# OSSISolarZ.net
KiCad netlist of a schematic drawn in EAGLE
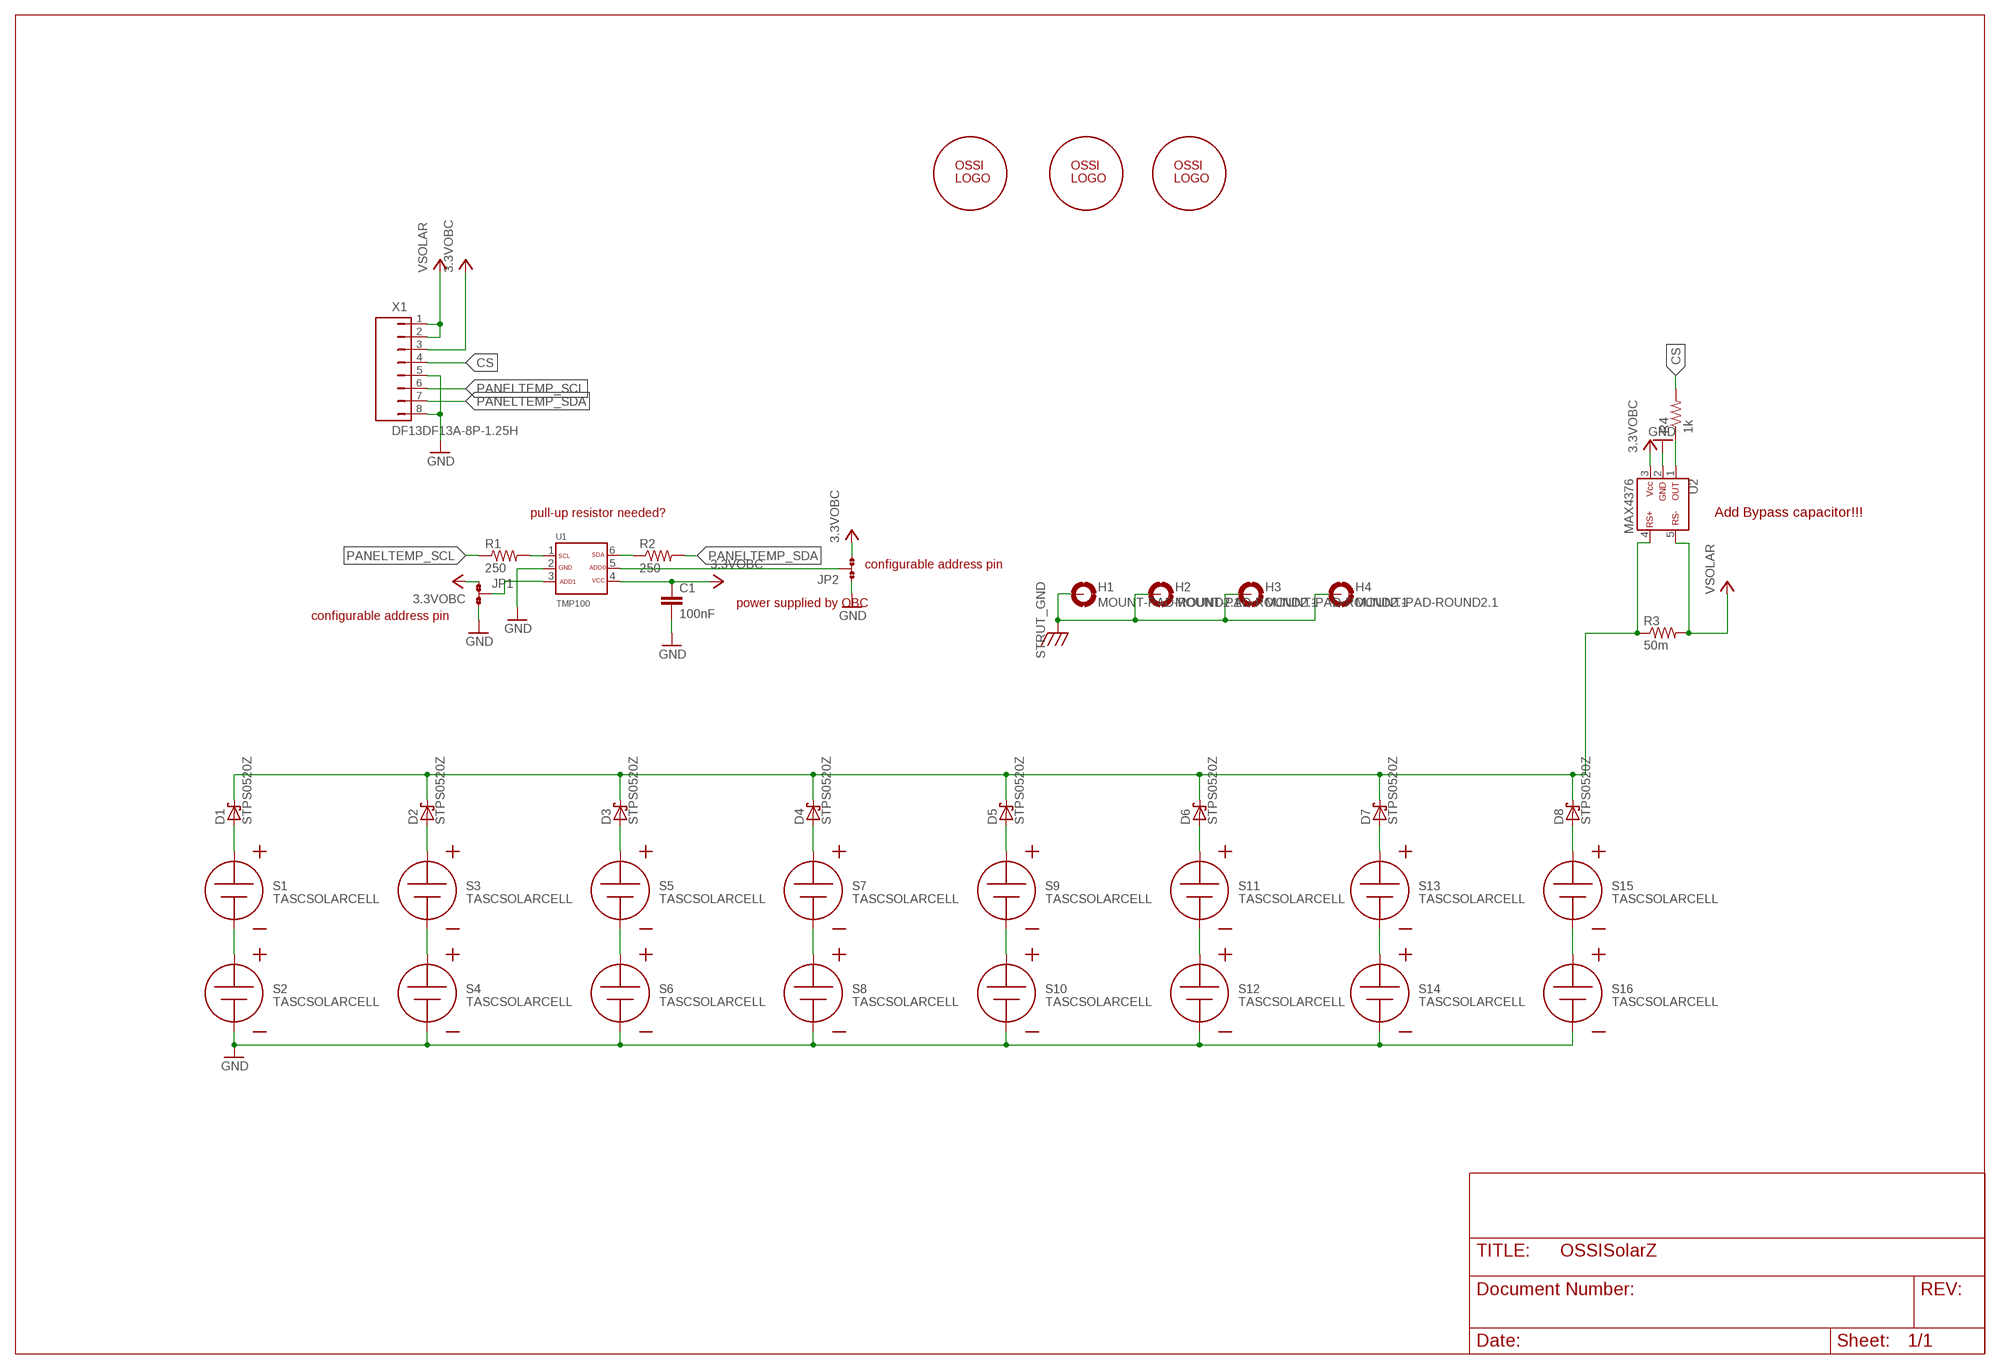
[diagram p0: schematic, sheet 1]

(export (version "E")
  (design (tool "Eeschema 10.0.6"))
  (components
    (comp (ref "C1")
      (value "100nF")
      (footprint "eagle-import:C0603(1608)")
      (libsource (lib "eagle-import") (part "C0603(1608)"))
    )
    (comp (ref "D1")
      (value "STPS0520Z")
      (footprint "eagle-import:SOD-123")
      (libsource (lib "eagle-import") (part "STPS0520Z"))
    )
    (comp (ref "D2")
      (value "STPS0520Z")
      (footprint "eagle-import:SOD-123")
      (libsource (lib "eagle-import") (part "STPS0520Z"))
    )
    (comp (ref "D3")
      (value "STPS0520Z")
      (footprint "eagle-import:SOD-123")
      (libsource (lib "eagle-import") (part "STPS0520Z"))
    )
    (comp (ref "D4")
      (value "STPS0520Z")
      (footprint "eagle-import:SOD-123")
      (libsource (lib "eagle-import") (part "STPS0520Z"))
    )
    (comp (ref "D5")
      (value "STPS0520Z")
      (footprint "eagle-import:SOD-123")
      (libsource (lib "eagle-import") (part "STPS0520Z"))
    )
    (comp (ref "D6")
      (value "STPS0520Z")
      (footprint "eagle-import:SOD-123")
      (libsource (lib "eagle-import") (part "STPS0520Z"))
    )
    (comp (ref "D7")
      (value "STPS0520Z")
      (footprint "eagle-import:SOD-123")
      (libsource (lib "eagle-import") (part "STPS0520Z"))
    )
    (comp (ref "D8")
      (value "STPS0520Z")
      (footprint "eagle-import:SOD-123")
      (libsource (lib "eagle-import") (part "STPS0520Z"))
    )
    (comp (ref "H1")
      (value "MOUNT-PAD-ROUND2.1")
      (footprint "eagle-import:2.1-PAD-ROUND")
      (libsource (lib "eagle-import") (part "MOUNT-PAD-ROUND2.1"))
    )
    (comp (ref "H2")
      (value "MOUNT-PAD-ROUND2.1")
      (footprint "eagle-import:2.1-PAD-ROUND")
      (libsource (lib "eagle-import") (part "MOUNT-PAD-ROUND2.1"))
    )
    (comp (ref "H3")
      (value "MOUNT-PAD-ROUND2.1")
      (footprint "eagle-import:2.1-PAD-ROUND")
      (libsource (lib "eagle-import") (part "MOUNT-PAD-ROUND2.1"))
    )
    (comp (ref "H4")
      (value "MOUNT-PAD-ROUND2.1")
      (footprint "eagle-import:2.1-PAD-ROUND")
      (libsource (lib "eagle-import") (part "MOUNT-PAD-ROUND2.1"))
    )
    (comp (ref "JP1")
      (value "JP2")
      (footprint "eagle-import:JP2SMD0603")
      (libsource (lib "eagle-import") (part "JP2"))
    )
    (comp (ref "JP2")
      (value "JP2")
      (footprint "eagle-import:JP2SMD0603")
      (libsource (lib "eagle-import") (part "JP2"))
    )
    (comp (ref "R1")
      (value "250")
      (footprint "eagle-import:R0603(1608)")
      (libsource (lib "eagle-import") (part "R0603(1608)"))
    )
    (comp (ref "R2")
      (value "250")
      (footprint "eagle-import:R0603(1608)")
      (libsource (lib "eagle-import") (part "R0603(1608)"))
    )
    (comp (ref "R3")
      (value "50m")
      (footprint "eagle-import:WSL1206")
      (libsource (lib "eagle-import") (part "RWSL1206"))
    )
    (comp (ref "R4")
      (value "1k")
      (footprint "eagle-import:R0603(1608)")
      (libsource (lib "eagle-import") (part "R0603(1608)"))
    )
    (comp (ref "S1")
      (value "TASCSOLARCELL")
      (footprint "eagle-import:TASCSOLARCELL")
      (libsource (lib "eagle-import") (part "TASCSOLARCELL"))
    )
    (comp (ref "S2")
      (value "TASCSOLARCELL")
      (footprint "eagle-import:TASCSOLARCELL")
      (libsource (lib "eagle-import") (part "TASCSOLARCELL"))
    )
    (comp (ref "S3")
      (value "TASCSOLARCELL")
      (footprint "eagle-import:TASCSOLARCELL")
      (libsource (lib "eagle-import") (part "TASCSOLARCELL"))
    )
    (comp (ref "S4")
      (value "TASCSOLARCELL")
      (footprint "eagle-import:TASCSOLARCELL")
      (libsource (lib "eagle-import") (part "TASCSOLARCELL"))
    )
    (comp (ref "S5")
      (value "TASCSOLARCELL")
      (footprint "eagle-import:TASCSOLARCELL")
      (libsource (lib "eagle-import") (part "TASCSOLARCELL"))
    )
    (comp (ref "S6")
      (value "TASCSOLARCELL")
      (footprint "eagle-import:TASCSOLARCELL")
      (libsource (lib "eagle-import") (part "TASCSOLARCELL"))
    )
    (comp (ref "S7")
      (value "TASCSOLARCELL")
      (footprint "eagle-import:TASCSOLARCELL")
      (libsource (lib "eagle-import") (part "TASCSOLARCELL"))
    )
    (comp (ref "S8")
      (value "TASCSOLARCELL")
      (footprint "eagle-import:TASCSOLARCELL")
      (libsource (lib "eagle-import") (part "TASCSOLARCELL"))
    )
    (comp (ref "S9")
      (value "TASCSOLARCELL")
      (footprint "eagle-import:TASCSOLARCELL")
      (libsource (lib "eagle-import") (part "TASCSOLARCELL"))
    )
    (comp (ref "S10")
      (value "TASCSOLARCELL")
      (footprint "eagle-import:TASCSOLARCELL")
      (libsource (lib "eagle-import") (part "TASCSOLARCELL"))
    )
    (comp (ref "S11")
      (value "TASCSOLARCELL")
      (footprint "eagle-import:TASCSOLARCELL")
      (libsource (lib "eagle-import") (part "TASCSOLARCELL"))
    )
    (comp (ref "S12")
      (value "TASCSOLARCELL")
      (footprint "eagle-import:TASCSOLARCELL")
      (libsource (lib "eagle-import") (part "TASCSOLARCELL"))
    )
    (comp (ref "S13")
      (value "TASCSOLARCELL")
      (footprint "eagle-import:TASCSOLARCELL")
      (libsource (lib "eagle-import") (part "TASCSOLARCELL"))
    )
    (comp (ref "S14")
      (value "TASCSOLARCELL")
      (footprint "eagle-import:TASCSOLARCELL")
      (libsource (lib "eagle-import") (part "TASCSOLARCELL"))
    )
    (comp (ref "S15")
      (value "TASCSOLARCELL")
      (footprint "eagle-import:TASCSOLARCELL")
      (libsource (lib "eagle-import") (part "TASCSOLARCELL"))
    )
    (comp (ref "S16")
      (value "TASCSOLARCELL")
      (footprint "eagle-import:TASCSOLARCELL")
      (libsource (lib "eagle-import") (part "TASCSOLARCELL"))
    )
    (comp (ref "U$1")
      (value "OSSILOGO-10")
      (footprint "eagle-import:OSSILOGO1010")
      (libsource (lib "eagle-import") (part "OSSILOGO-10"))
    )
    (comp (ref "U$2")
      (value "OSSILOGO-10")
      (footprint "eagle-import:OSSILOGO1010")
      (libsource (lib "eagle-import") (part "OSSILOGO-10"))
    )
    (comp (ref "U$3")
      (value "OSSITAGCC")
      (footprint "eagle-import:CCLOGO")
      (libsource (lib "eagle-import") (part "OSSITAGCC"))
    )
    (comp (ref "U1")
      (value "TMP100")
      (footprint "eagle-import:SOT23-6DBV")
      (libsource (lib "eagle-import") (part "TMP100"))
    )
    (comp (ref "U2")
      (value "MAX4376")
      (footprint "eagle-import:SOT23-5DBV")
      (libsource (lib "eagle-import") (part "MAX4376"))
    )
    (comp (ref "X1")
      (value "DF13DF13A-8P-1.25H")
      (footprint "eagle-import:DF13A-8P")
      (libsource (lib "eagle-import") (part "DF13DF13A-8P-1.25H"))
    )
  )
  (nets
    (net (code "1") (name "3.3VOBC") (class "Default")
      (node (ref "C1") (pin "1") (pinfunction "1_1") (pintype "passive"))
      (node (ref "JP1") (pin "1") (pinfunction "1_1") (pintype "passive"))
      (node (ref "JP2") (pin "3") (pinfunction "3_3") (pintype "passive"))
      (node (ref "U1") (pin "4") (pinfunction "4_4") (pintype "bidirectional"))
      (node (ref "U2") (pin "3") (pinfunction "P$3_3") (pintype "power_in"))
      (node (ref "X1") (pin "3") (pinfunction "3_3") (pintype "passive"))
    )
    (net (code "2") (name "CS") (class "Default")
      (node (ref "R4") (pin "2") (pinfunction "2_2") (pintype "passive"))
      (node (ref "X1") (pin "4") (pinfunction "4_4") (pintype "passive"))
    )
    (net (code "3") (name "GND") (class "Default")
      (node (ref "C1") (pin "2") (pinfunction "2_2") (pintype "passive"))
      (node (ref "JP1") (pin "3") (pinfunction "3_3") (pintype "passive"))
      (node (ref "JP2") (pin "1") (pinfunction "1_1") (pintype "passive"))
      (node (ref "S10") (pin "N") (pinfunction "N_N") (pintype "power_in"))
      (node (ref "S12") (pin "N") (pinfunction "N_N") (pintype "power_in"))
      (node (ref "S14") (pin "N") (pinfunction "N_N") (pintype "power_in"))
      (node (ref "S16") (pin "N") (pinfunction "N_N") (pintype "power_in"))
      (node (ref "S2") (pin "N") (pinfunction "N_N") (pintype "power_in"))
      (node (ref "S4") (pin "N") (pinfunction "N_N") (pintype "power_in"))
      (node (ref "S6") (pin "N") (pinfunction "N_N") (pintype "power_in"))
      (node (ref "S8") (pin "N") (pinfunction "N_N") (pintype "power_in"))
      (node (ref "U1") (pin "2") (pinfunction "2_2") (pintype "bidirectional"))
      (node (ref "U2") (pin "2") (pinfunction "P$2_2") (pintype "power_in"))
      (node (ref "X1") (pin "5") (pinfunction "5_5") (pintype "passive"))
      (node (ref "X1") (pin "8") (pinfunction "8_8") (pintype "passive"))
    )
    (net (code "4") (name "Net-(D1-PadA)") (class "Default")
      (node (ref "D1") (pin "A") (pinfunction "A_A") (pintype "passive"))
      (node (ref "S1") (pin "P") (pinfunction "P_P") (pintype "power_in"))
    )
    (net (code "5") (name "Net-(D2-PadA)") (class "Default")
      (node (ref "D2") (pin "A") (pinfunction "A_A") (pintype "passive"))
      (node (ref "S3") (pin "P") (pinfunction "P_P") (pintype "power_in"))
    )
    (net (code "6") (name "Net-(D3-PadA)") (class "Default")
      (node (ref "D3") (pin "A") (pinfunction "A_A") (pintype "passive"))
      (node (ref "S5") (pin "P") (pinfunction "P_P") (pintype "power_in"))
    )
    (net (code "7") (name "Net-(D4-PadA)") (class "Default")
      (node (ref "D4") (pin "A") (pinfunction "A_A") (pintype "passive"))
      (node (ref "S7") (pin "P") (pinfunction "P_P") (pintype "power_in"))
    )
    (net (code "8") (name "Net-(D5-PadA)") (class "Default")
      (node (ref "D5") (pin "A") (pinfunction "A_A") (pintype "passive"))
      (node (ref "S9") (pin "P") (pinfunction "P_P") (pintype "power_in"))
    )
    (net (code "9") (name "Net-(D6-PadA)") (class "Default")
      (node (ref "D6") (pin "A") (pinfunction "A_A") (pintype "passive"))
      (node (ref "S11") (pin "P") (pinfunction "P_P") (pintype "power_in"))
    )
    (net (code "10") (name "Net-(D7-PadA)") (class "Default")
      (node (ref "D7") (pin "A") (pinfunction "A_A") (pintype "passive"))
      (node (ref "S13") (pin "P") (pinfunction "P_P") (pintype "power_in"))
    )
    (net (code "11") (name "Net-(D8-PadA)") (class "Default")
      (node (ref "D8") (pin "A") (pinfunction "A_A") (pintype "passive"))
      (node (ref "S15") (pin "P") (pinfunction "P_P") (pintype "power_in"))
    )
    (net (code "12") (name "Net-(JP1-Pad2)") (class "Default")
      (node (ref "JP1") (pin "2") (pinfunction "2_2") (pintype "passive"))
      (node (ref "U1") (pin "3") (pinfunction "3_3") (pintype "bidirectional"))
    )
    (net (code "13") (name "Net-(JP2-Pad2)") (class "Default")
      (node (ref "JP2") (pin "2") (pinfunction "2_2") (pintype "passive"))
      (node (ref "U1") (pin "5") (pinfunction "5_5") (pintype "bidirectional"))
    )
    (net (code "14") (name "Net-(R1-Pad2)") (class "Default")
      (node (ref "R1") (pin "2") (pinfunction "2_2") (pintype "passive"))
      (node (ref "U1") (pin "1") (pinfunction "1_1") (pintype "bidirectional"))
    )
    (net (code "15") (name "Net-(R2-Pad1)") (class "Default")
      (node (ref "R2") (pin "1") (pinfunction "1_1") (pintype "passive"))
      (node (ref "U1") (pin "6") (pinfunction "6_6") (pintype "bidirectional"))
    )
    (net (code "16") (name "Net-(R3-1)") (class "Default")
      (node (ref "D1") (pin "C") (pinfunction "C_C") (pintype "passive"))
      (node (ref "D2") (pin "C") (pinfunction "C_C") (pintype "passive"))
      (node (ref "D3") (pin "C") (pinfunction "C_C") (pintype "passive"))
      (node (ref "D4") (pin "C") (pinfunction "C_C") (pintype "passive"))
      (node (ref "D5") (pin "C") (pinfunction "C_C") (pintype "passive"))
      (node (ref "D6") (pin "C") (pinfunction "C_C") (pintype "passive"))
      (node (ref "D7") (pin "C") (pinfunction "C_C") (pintype "passive"))
      (node (ref "D8") (pin "C") (pinfunction "C_C") (pintype "passive"))
      (node (ref "R3") (pin "P$1") (pinfunction "1_P$1") (pintype "passive"))
      (node (ref "U2") (pin "4") (pinfunction "P$4_4") (pintype "input"))
    )
    (net (code "17") (name "Net-(S1-PadN)") (class "Default")
      (node (ref "S1") (pin "N") (pinfunction "N_N") (pintype "power_in"))
      (node (ref "S2") (pin "P") (pinfunction "P_P") (pintype "power_in"))
    )
    (net (code "18") (name "Net-(S3-PadN)") (class "Default")
      (node (ref "S3") (pin "N") (pinfunction "N_N") (pintype "power_in"))
      (node (ref "S4") (pin "P") (pinfunction "P_P") (pintype "power_in"))
    )
    (net (code "19") (name "Net-(S5-PadN)") (class "Default")
      (node (ref "S5") (pin "N") (pinfunction "N_N") (pintype "power_in"))
      (node (ref "S6") (pin "P") (pinfunction "P_P") (pintype "power_in"))
    )
    (net (code "20") (name "Net-(S7-PadN)") (class "Default")
      (node (ref "S7") (pin "N") (pinfunction "N_N") (pintype "power_in"))
      (node (ref "S8") (pin "P") (pinfunction "P_P") (pintype "power_in"))
    )
    (net (code "21") (name "Net-(S10-PadP)") (class "Default")
      (node (ref "S10") (pin "P") (pinfunction "P_P") (pintype "power_in"))
      (node (ref "S9") (pin "N") (pinfunction "N_N") (pintype "power_in"))
    )
    (net (code "22") (name "Net-(S11-PadN)") (class "Default")
      (node (ref "S11") (pin "N") (pinfunction "N_N") (pintype "power_in"))
      (node (ref "S12") (pin "P") (pinfunction "P_P") (pintype "power_in"))
    )
    (net (code "23") (name "Net-(S13-PadN)") (class "Default")
      (node (ref "S13") (pin "N") (pinfunction "N_N") (pintype "power_in"))
      (node (ref "S14") (pin "P") (pinfunction "P_P") (pintype "power_in"))
    )
    (net (code "24") (name "Net-(S15-PadN)") (class "Default")
      (node (ref "S15") (pin "N") (pinfunction "N_N") (pintype "power_in"))
      (node (ref "S16") (pin "P") (pinfunction "P_P") (pintype "power_in"))
    )
    (net (code "25") (name "Net-(U2-P$1)") (class "Default")
      (node (ref "R4") (pin "1") (pinfunction "1_1") (pintype "passive"))
      (node (ref "U2") (pin "1") (pinfunction "P$1_1") (pintype "output"))
    )
    (net (code "26") (name "PANELTEMP_SCL") (class "Default")
      (node (ref "R1") (pin "1") (pinfunction "1_1") (pintype "passive"))
      (node (ref "X1") (pin "6") (pinfunction "6_6") (pintype "passive"))
    )
    (net (code "27") (name "PANELTEMP_SDA") (class "Default")
      (node (ref "R2") (pin "2") (pinfunction "2_2") (pintype "passive"))
      (node (ref "X1") (pin "7") (pinfunction "7_7") (pintype "passive"))
    )
    (net (code "28") (name "STRUT_GND") (class "Default")
      (node (ref "H1") (pin "B3,2") (pinfunction "MOUNT_B3,2") (pintype "passive"))
      (node (ref "H2") (pin "B3,2") (pinfunction "MOUNT_B3,2") (pintype "passive"))
      (node (ref "H3") (pin "B3,2") (pinfunction "MOUNT_B3,2") (pintype "passive"))
      (node (ref "H4") (pin "B3,2") (pinfunction "MOUNT_B3,2") (pintype "passive"))
    )
    (net (code "29") (name "VSOLAR") (class "Default")
      (node (ref "R3") (pin "P$2") (pinfunction "2_P$2") (pintype "passive"))
      (node (ref "U2") (pin "5") (pinfunction "P$5_5") (pintype "input"))
      (node (ref "X1") (pin "1") (pinfunction "1_1") (pintype "passive"))
      (node (ref "X1") (pin "2") (pinfunction "2_2") (pintype "passive"))
    )
  )
)
